# schematicEagle.net
KiCad netlist of a schematic drawn in EAGLE
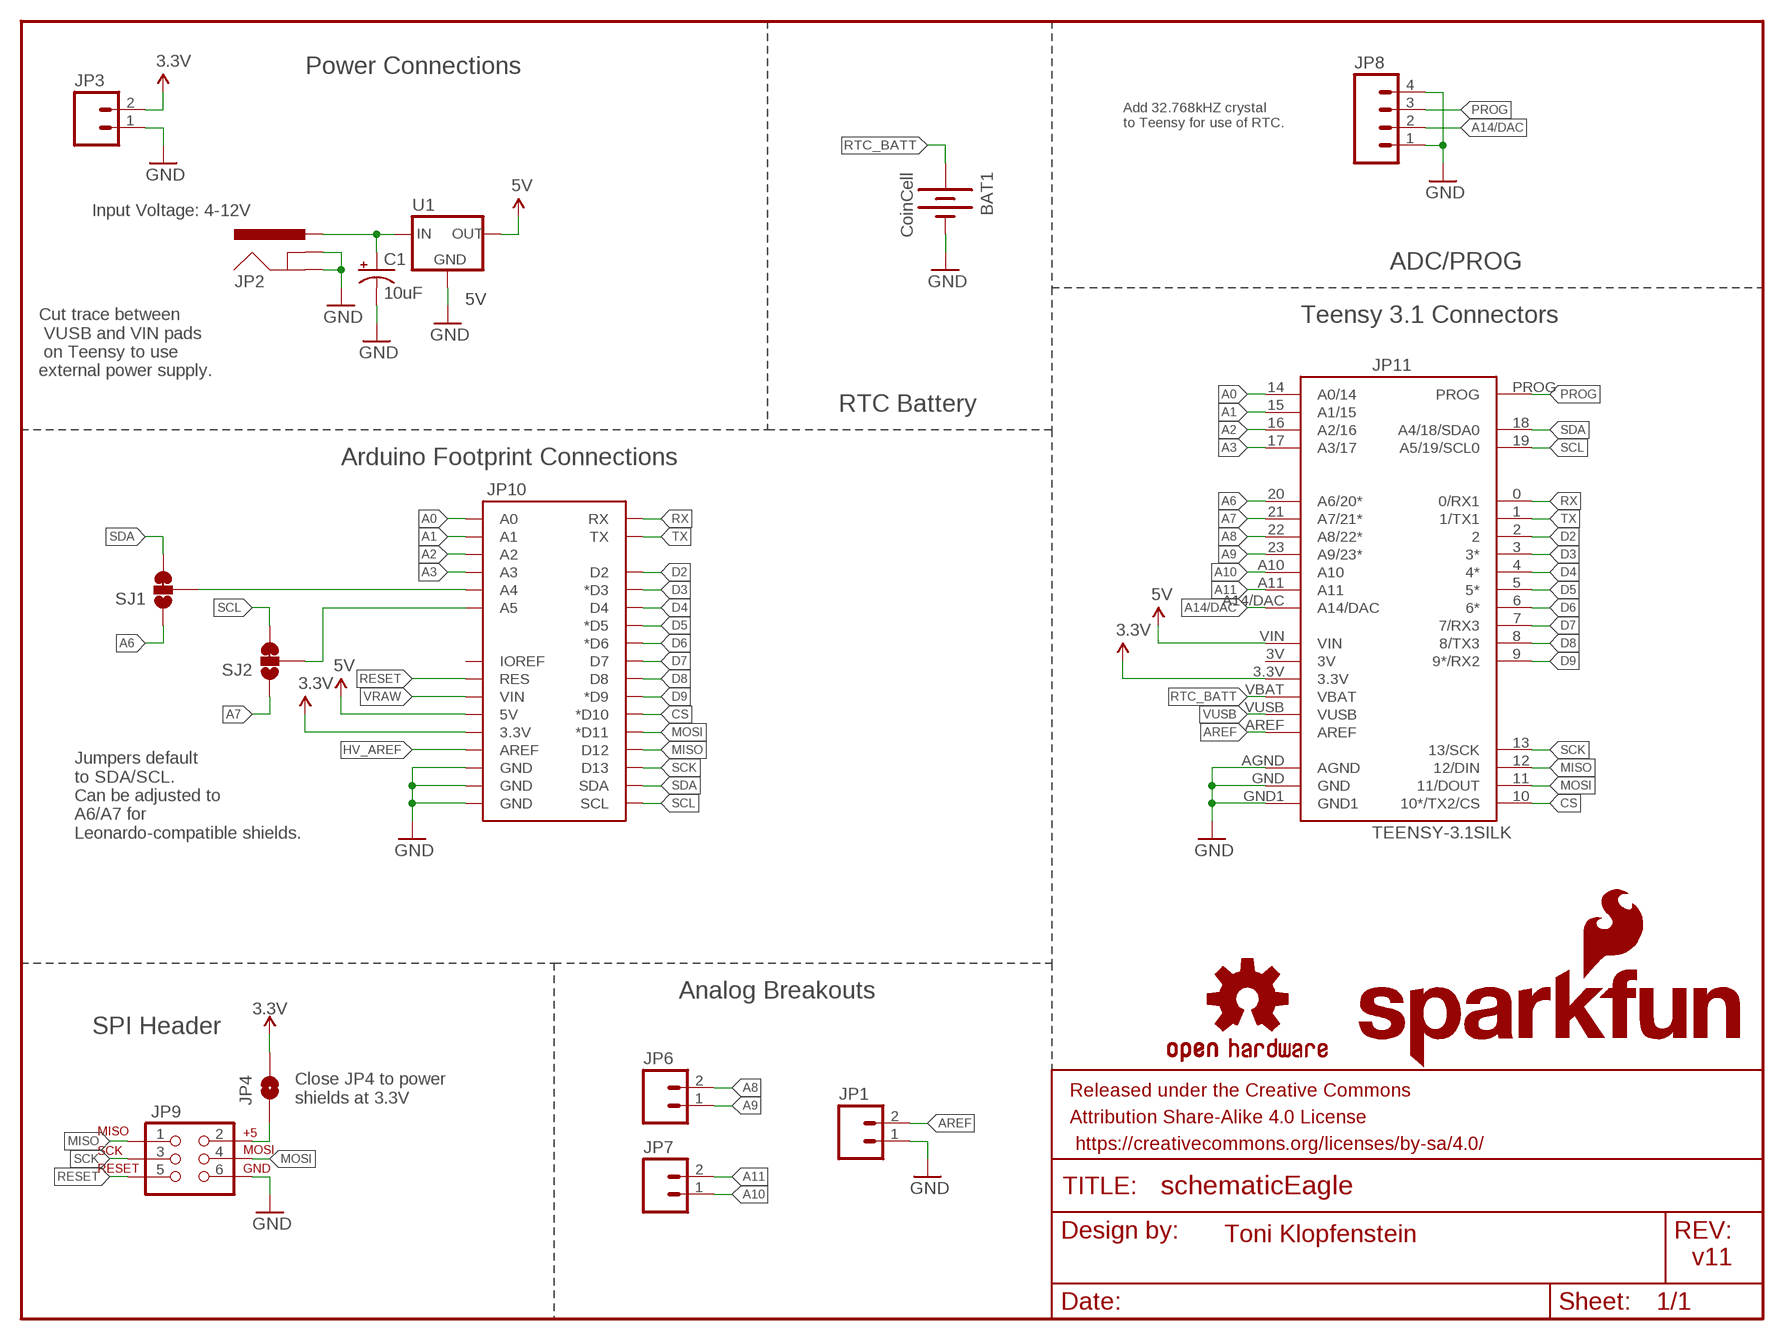
[diagram p0: schematic, sheet 1]

(export (version "E")
  (design (tool "Eeschema 10.0.6"))
  (components
    (comp (ref "BAT1")
      (value "CoinCell")
      (footprint "eagle-import:BATTCON_12MM_PTH")
      (libsource (lib "eagle-import") (part "BATTERY12PTH"))
    )
    (comp (ref "C1")
      (value "10uF")
      (footprint "eagle-import:CPOL-RADIAL-10UF-25V")
      (libsource (lib "eagle-import") (part "10UF-25V-20%(PTH)"))
    )
    (comp (ref "FRAME1")
      (value "FRAME-LETTER")
      (footprint "eagle-import:CREATIVE_COMMONS")
      (libsource (lib "eagle-import") (part "FRAME-LETTER"))
    )
    (comp (ref "JP1")
      (value "M02PTH")
      (footprint "eagle-import:1X02")
      (libsource (lib "eagle-import") (part "M02PTH"))
    )
    (comp (ref "JP2")
      (value "POWER_JACKPTH_LOCK")
      (footprint "eagle-import:POWER_JACK_PTH_LOCK")
      (libsource (lib "eagle-import") (part "POWER_JACKPTH_LOCK"))
    )
    (comp (ref "JP3")
      (value "JST2")
      (footprint "eagle-import:JST-2-PTH")
      (libsource (lib "eagle-import") (part "M02JST-PTH-2"))
    )
    (comp (ref "JP4")
      (value "JUMPER-SMT_2_NO_SILK")
      (footprint "eagle-import:SMT-JUMPER_2_NO_SILK")
      (libsource (lib "eagle-import") (part "JUMPER-SMT_2_NO_SILK"))
    )
    (comp (ref "JP6")
      (value "M02PTH")
      (footprint "eagle-import:1X02")
      (libsource (lib "eagle-import") (part "M02PTH"))
    )
    (comp (ref "JP7")
      (value "M02PTH")
      (footprint "eagle-import:1X02")
      (libsource (lib "eagle-import") (part "M02PTH"))
    )
    (comp (ref "JP8")
      (value "M04PTH")
      (footprint "eagle-import:1X04")
      (libsource (lib "eagle-import") (part "M04PTH"))
    )
    (comp (ref "JP9")
      (value "AVR_SPI_PRG_6PTH")
      (footprint "eagle-import:2X3")
      (libsource (lib "eagle-import") (part "AVR_SPI_PRG_6PTH"))
    )
    (comp (ref "JP10")
      (value "ARDUINO_R3_SHIELDUNO_R3_SHIELD_HOLES")
      (footprint "eagle-import:UNO_R3_SHIELD_HOLES")
      (libsource (lib "eagle-import") (part "ARDUINO_R3_SHIELDUNO_R3_SHIELD_HOLES"))
    )
    (comp (ref "JP11")
      (value "TEENSY-3.1SILK")
      (footprint "eagle-import:TEENSY-3.1")
      (libsource (lib "eagle-import") (part "TEENSY-3.1SILK"))
    )
    (comp (ref "LOGO1")
      (value "SFE_LOGO_NAME_FLAME.1_INCH")
      (footprint "eagle-import:SFE_LOGO_NAME_FLAME_.1")
      (libsource (lib "eagle-import") (part "SFE_LOGO_NAME_FLAME.1_INCH"))
    )
    (comp (ref "LOGO2")
      (value "OSHW-LOGOM")
      (footprint "eagle-import:OSHW-LOGO-M")
      (libsource (lib "eagle-import") (part "OSHW-LOGOM"))
    )
    (comp (ref "SJ1")
      (value "JUMPER-PAD-3-2OF3_NC_BY_TRACE_SMALL")
      (footprint "eagle-import:PAD-JUMPER-3-2OF3_NC_BY_TRACE_YES_SILK_FULL_BOX")
      (libsource (lib "eagle-import") (part "JUMPER-PAD-3-2OF3_NC_BY_TRACE_SMALL"))
    )
    (comp (ref "SJ2")
      (value "JUMPER-PAD-3-2OF3_NC_BY_TRACE_SMALL")
      (footprint "eagle-import:PAD-JUMPER-3-2OF3_NC_BY_TRACE_YES_SILK_FULL_BOX")
      (libsource (lib "eagle-import") (part "JUMPER-PAD-3-2OF3_NC_BY_TRACE_SMALL"))
    )
    (comp (ref "U1")
      (value "5V")
      (footprint "eagle-import:TO-220-ALT")
      (libsource (lib "eagle-import") (part "V_REG_78XX-TO-220"))
    )
  )
  (nets
    (net (code "1") (name "3.3V") (class "Default")
      (node (ref "JP10") (pin "3.3V") (pinfunction "3.3V_3.3V") (pintype "bidirectional"))
      (node (ref "JP11") (pin "3.3V") (pinfunction "3.3V_3.3V") (pintype "bidirectional"))
      (node (ref "JP3") (pin "2") (pinfunction "2_2") (pintype "passive"))
      (node (ref "JP4") (pin "2") (pinfunction "2_2") (pintype "passive"))
    )
    (net (code "2") (name "5V") (class "Default")
      (node (ref "JP10") (pin "5V") (pinfunction "5V_5V") (pintype "bidirectional"))
      (node (ref "JP11") (pin "VIN") (pinfunction "VIN_VIN") (pintype "bidirectional"))
      (node (ref "U1") (pin "OUT") (pinfunction "OUT_OUT") (pintype "output"))
    )
    (net (code "3") (name "A0") (class "Default")
      (node (ref "JP10") (pin "A0") (pinfunction "A0_A0") (pintype "bidirectional"))
      (node (ref "JP11") (pin "14") (pinfunction "A0/14_14") (pintype "bidirectional"))
    )
    (net (code "4") (name "A1") (class "Default")
      (node (ref "JP10") (pin "A1") (pinfunction "A1_A1") (pintype "bidirectional"))
      (node (ref "JP11") (pin "15") (pinfunction "A1/15_15") (pintype "bidirectional"))
    )
    (net (code "5") (name "A2") (class "Default")
      (node (ref "JP10") (pin "A2") (pinfunction "A2_A2") (pintype "bidirectional"))
      (node (ref "JP11") (pin "16") (pinfunction "A2/16_16") (pintype "bidirectional"))
    )
    (net (code "6") (name "A3") (class "Default")
      (node (ref "JP10") (pin "A3") (pinfunction "A3_A3") (pintype "bidirectional"))
      (node (ref "JP11") (pin "17") (pinfunction "A3/17_17") (pintype "bidirectional"))
    )
    (net (code "7") (name "A6") (class "Default")
      (node (ref "JP11") (pin "20") (pinfunction "A6/20*_20") (pintype "bidirectional"))
      (node (ref "SJ1") (pin "1") (pinfunction "1_1") (pintype "passive"))
    )
    (net (code "8") (name "A7") (class "Default")
      (node (ref "JP11") (pin "21") (pinfunction "A7/21*_21") (pintype "bidirectional"))
      (node (ref "SJ2") (pin "1") (pinfunction "1_1") (pintype "passive"))
    )
    (net (code "9") (name "A8") (class "Default")
      (node (ref "JP11") (pin "22") (pinfunction "A8/22*_22") (pintype "bidirectional"))
      (node (ref "JP6") (pin "2") (pinfunction "2_2") (pintype "passive"))
    )
    (net (code "10") (name "A9") (class "Default")
      (node (ref "JP11") (pin "23") (pinfunction "A9/23*_23") (pintype "bidirectional"))
      (node (ref "JP6") (pin "1") (pinfunction "1_1") (pintype "passive"))
    )
    (net (code "11") (name "A10") (class "Default")
      (node (ref "JP11") (pin "A10") (pinfunction "A10_A10") (pintype "bidirectional"))
      (node (ref "JP7") (pin "1") (pinfunction "1_1") (pintype "passive"))
    )
    (net (code "12") (name "A11") (class "Default")
      (node (ref "JP11") (pin "A11") (pinfunction "A11_A11") (pintype "bidirectional"))
      (node (ref "JP7") (pin "2") (pinfunction "2_2") (pintype "passive"))
    )
    (net (code "13") (name "A14{slash}DAC") (class "Default")
      (node (ref "JP11") (pin "A14/DAC") (pinfunction "A14/DAC_A14/DAC") (pintype "bidirectional"))
      (node (ref "JP8") (pin "2") (pinfunction "2_2") (pintype "passive"))
    )
    (net (code "14") (name "AREF") (class "Default")
      (node (ref "JP1") (pin "2") (pinfunction "2_2") (pintype "passive"))
      (node (ref "JP11") (pin "AREF") (pinfunction "AREF_AREF") (pintype "bidirectional"))
    )
    (net (code "15") (name "CS") (class "Default")
      (node (ref "JP10") (pin "D10") (pinfunction "*D10_D10") (pintype "bidirectional"))
      (node (ref "JP11") (pin "10") (pinfunction "10*/TX2/CS_10") (pintype "bidirectional"))
    )
    (net (code "16") (name "D2") (class "Default")
      (node (ref "JP10") (pin "D2") (pinfunction "D2_D2") (pintype "bidirectional"))
      (node (ref "JP11") (pin "2") (pinfunction "2_2") (pintype "bidirectional"))
    )
    (net (code "17") (name "D3") (class "Default")
      (node (ref "JP10") (pin "D3") (pinfunction "*D3_D3") (pintype "bidirectional"))
      (node (ref "JP11") (pin "3") (pinfunction "3*_3") (pintype "bidirectional"))
    )
    (net (code "18") (name "D4") (class "Default")
      (node (ref "JP10") (pin "D4") (pinfunction "D4_D4") (pintype "bidirectional"))
      (node (ref "JP11") (pin "4") (pinfunction "4*_4") (pintype "bidirectional"))
    )
    (net (code "19") (name "D5") (class "Default")
      (node (ref "JP10") (pin "D5") (pinfunction "*D5_D5") (pintype "bidirectional"))
      (node (ref "JP11") (pin "5") (pinfunction "5*_5") (pintype "bidirectional"))
    )
    (net (code "20") (name "D6") (class "Default")
      (node (ref "JP10") (pin "D6") (pinfunction "*D6_D6") (pintype "bidirectional"))
      (node (ref "JP11") (pin "6") (pinfunction "6*_6") (pintype "bidirectional"))
    )
    (net (code "21") (name "D7") (class "Default")
      (node (ref "JP10") (pin "D7") (pinfunction "D7_D7") (pintype "bidirectional"))
      (node (ref "JP11") (pin "7") (pinfunction "7/RX3_7") (pintype "bidirectional"))
    )
    (net (code "22") (name "D8") (class "Default")
      (node (ref "JP10") (pin "D8") (pinfunction "D8_D8") (pintype "bidirectional"))
      (node (ref "JP11") (pin "8") (pinfunction "8/TX3_8") (pintype "bidirectional"))
    )
    (net (code "23") (name "D9") (class "Default")
      (node (ref "JP10") (pin "D9") (pinfunction "*D9_D9") (pintype "bidirectional"))
      (node (ref "JP11") (pin "9") (pinfunction "9*/RX2_9") (pintype "bidirectional"))
    )
    (net (code "24") (name "GND") (class "Default")
      (node (ref "BAT1") (pin "GND") (pinfunction "-_GND") (pintype "power_in"))
      (node (ref "C1") (pin "2") (pinfunction "-_2") (pintype "passive"))
      (node (ref "JP1") (pin "1") (pinfunction "1_1") (pintype "passive"))
      (node (ref "JP10") (pin "GND@0") (pinfunction "GND_GND@0") (pintype "bidirectional"))
      (node (ref "JP10") (pin "GND@1") (pinfunction "GND_GND@1") (pintype "bidirectional"))
      (node (ref "JP10") (pin "GND@2") (pinfunction "GND_GND@2") (pintype "bidirectional"))
      (node (ref "JP11") (pin "AGND") (pinfunction "AGND_AGND") (pintype "bidirectional"))
      (node (ref "JP11") (pin "GND") (pinfunction "GND_GND") (pintype "bidirectional"))
      (node (ref "JP11") (pin "GND1") (pinfunction "GND1_GND1") (pintype "bidirectional"))
      (node (ref "JP2") (pin "GND") (pinfunction "GND_GND") (pintype "bidirectional"))
      (node (ref "JP2") (pin "GNDBREAK") (pinfunction "GNDBREAK_GNDBREAK") (pintype "bidirectional"))
      (node (ref "JP3") (pin "1") (pinfunction "1_1") (pintype "passive"))
      (node (ref "JP8") (pin "1") (pinfunction "1_1") (pintype "passive"))
      (node (ref "JP8") (pin "4") (pinfunction "4_4") (pintype "passive"))
      (node (ref "JP9") (pin "6") (pinfunction "6_6") (pintype "passive"))
      (node (ref "U1") (pin "GND") (pinfunction "GND_GND") (pintype "input"))
    )
    (net (code "25") (name "HV_AREF") (class "Default")
      (node (ref "JP10") (pin "AREF") (pinfunction "AREF_AREF") (pintype "bidirectional"))
    )
    (net (code "26") (name "MISO") (class "Default")
      (node (ref "JP10") (pin "D12") (pinfunction "D12_D12") (pintype "bidirectional"))
      (node (ref "JP11") (pin "12") (pinfunction "12/DIN_12") (pintype "bidirectional"))
      (node (ref "JP9") (pin "1") (pinfunction "1_1") (pintype "passive"))
    )
    (net (code "27") (name "MOSI") (class "Default")
      (node (ref "JP10") (pin "D11") (pinfunction "*D11_D11") (pintype "bidirectional"))
      (node (ref "JP11") (pin "11") (pinfunction "11/DOUT_11") (pintype "bidirectional"))
      (node (ref "JP9") (pin "4") (pinfunction "4_4") (pintype "passive"))
    )
    (net (code "28") (name "Net-(JP4-Pad1)") (class "Default")
      (node (ref "JP4") (pin "1") (pinfunction "1_1") (pintype "passive"))
      (node (ref "JP9") (pin "2") (pinfunction "2_2") (pintype "passive"))
    )
    (net (code "29") (name "Net-(JP10-PadA4)") (class "Default")
      (node (ref "JP10") (pin "A4") (pinfunction "A4_A4") (pintype "bidirectional"))
      (node (ref "SJ1") (pin "2") (pinfunction "2_2") (pintype "passive"))
    )
    (net (code "30") (name "Net-(JP10-PadA5)") (class "Default")
      (node (ref "JP10") (pin "A5") (pinfunction "A5_A5") (pintype "bidirectional"))
      (node (ref "SJ2") (pin "2") (pinfunction "2_2") (pintype "passive"))
    )
    (net (code "31") (name "PROG") (class "Default")
      (node (ref "JP11") (pin "PROG") (pinfunction "PROG_PROG") (pintype "bidirectional"))
      (node (ref "JP8") (pin "3") (pinfunction "3_3") (pintype "passive"))
    )
    (net (code "32") (name "RESET") (class "Default")
      (node (ref "JP10") (pin "RES") (pinfunction "RES_RES") (pintype "bidirectional"))
      (node (ref "JP9") (pin "5") (pinfunction "5_5") (pintype "passive"))
    )
    (net (code "33") (name "RTC_BATT") (class "Default")
      (node (ref "BAT1") (pin "VCC@1") (pinfunction "+_VCC@1") (pintype "power_in"))
      (node (ref "JP11") (pin "VBAT") (pinfunction "VBAT_VBAT") (pintype "bidirectional"))
    )
    (net (code "34") (name "RX") (class "Default")
      (node (ref "JP10") (pin "RX") (pinfunction "RX_RX") (pintype "bidirectional"))
      (node (ref "JP11") (pin "0") (pinfunction "0/RX1_0") (pintype "bidirectional"))
    )
    (net (code "35") (name "SCK") (class "Default")
      (node (ref "JP10") (pin "D13") (pinfunction "D13_D13") (pintype "bidirectional"))
      (node (ref "JP11") (pin "13") (pinfunction "13/SCK_13") (pintype "bidirectional"))
      (node (ref "JP9") (pin "3") (pinfunction "3_3") (pintype "passive"))
    )
    (net (code "36") (name "SCL") (class "Default")
      (node (ref "JP10") (pin "SCL") (pinfunction "SCL_SCL") (pintype "bidirectional"))
      (node (ref "JP11") (pin "19") (pinfunction "A5/19/SCL0_19") (pintype "bidirectional"))
      (node (ref "SJ2") (pin "3") (pinfunction "3_3") (pintype "passive"))
    )
    (net (code "37") (name "SDA") (class "Default")
      (node (ref "JP10") (pin "SDA") (pinfunction "SDA_SDA") (pintype "bidirectional"))
      (node (ref "JP11") (pin "18") (pinfunction "A4/18/SDA0_18") (pintype "bidirectional"))
      (node (ref "SJ1") (pin "3") (pinfunction "3_3") (pintype "passive"))
    )
    (net (code "38") (name "TX") (class "Default")
      (node (ref "JP10") (pin "TX") (pinfunction "TX_TX") (pintype "bidirectional"))
      (node (ref "JP11") (pin "1") (pinfunction "1/TX1_1") (pintype "bidirectional"))
    )
    (net (code "39") (name "VRAW") (class "Default")
      (node (ref "C1") (pin "1") (pinfunction "+_1") (pintype "passive"))
      (node (ref "JP10") (pin "VIN") (pinfunction "VIN_VIN") (pintype "bidirectional"))
      (node (ref "JP2") (pin "PWR") (pinfunction "PWR_PWR") (pintype "bidirectional"))
      (node (ref "U1") (pin "IN") (pinfunction "IN_IN") (pintype "input"))
    )
    (net (code "40") (name "VUSB") (class "Default")
      (node (ref "JP11") (pin "VUSB") (pinfunction "VUSB_VUSB") (pintype "bidirectional"))
    )
    (net (code "41") (name "unconnected-(JP10-PadIOREF)") (class "Default")
      (node (ref "JP10") (pin "IOREF") (pinfunction "IOREF_IOREF") (pintype "bidirectional"))
    )
    (net (code "42") (name "unconnected-(JP11-Pad3V)") (class "Default")
      (node (ref "JP11") (pin "3V") (pinfunction "3V_3V") (pintype "bidirectional"))
    )
  )
)
